# Sheet8.net
KiCad netlist of a schematic drawn in Altium Designer
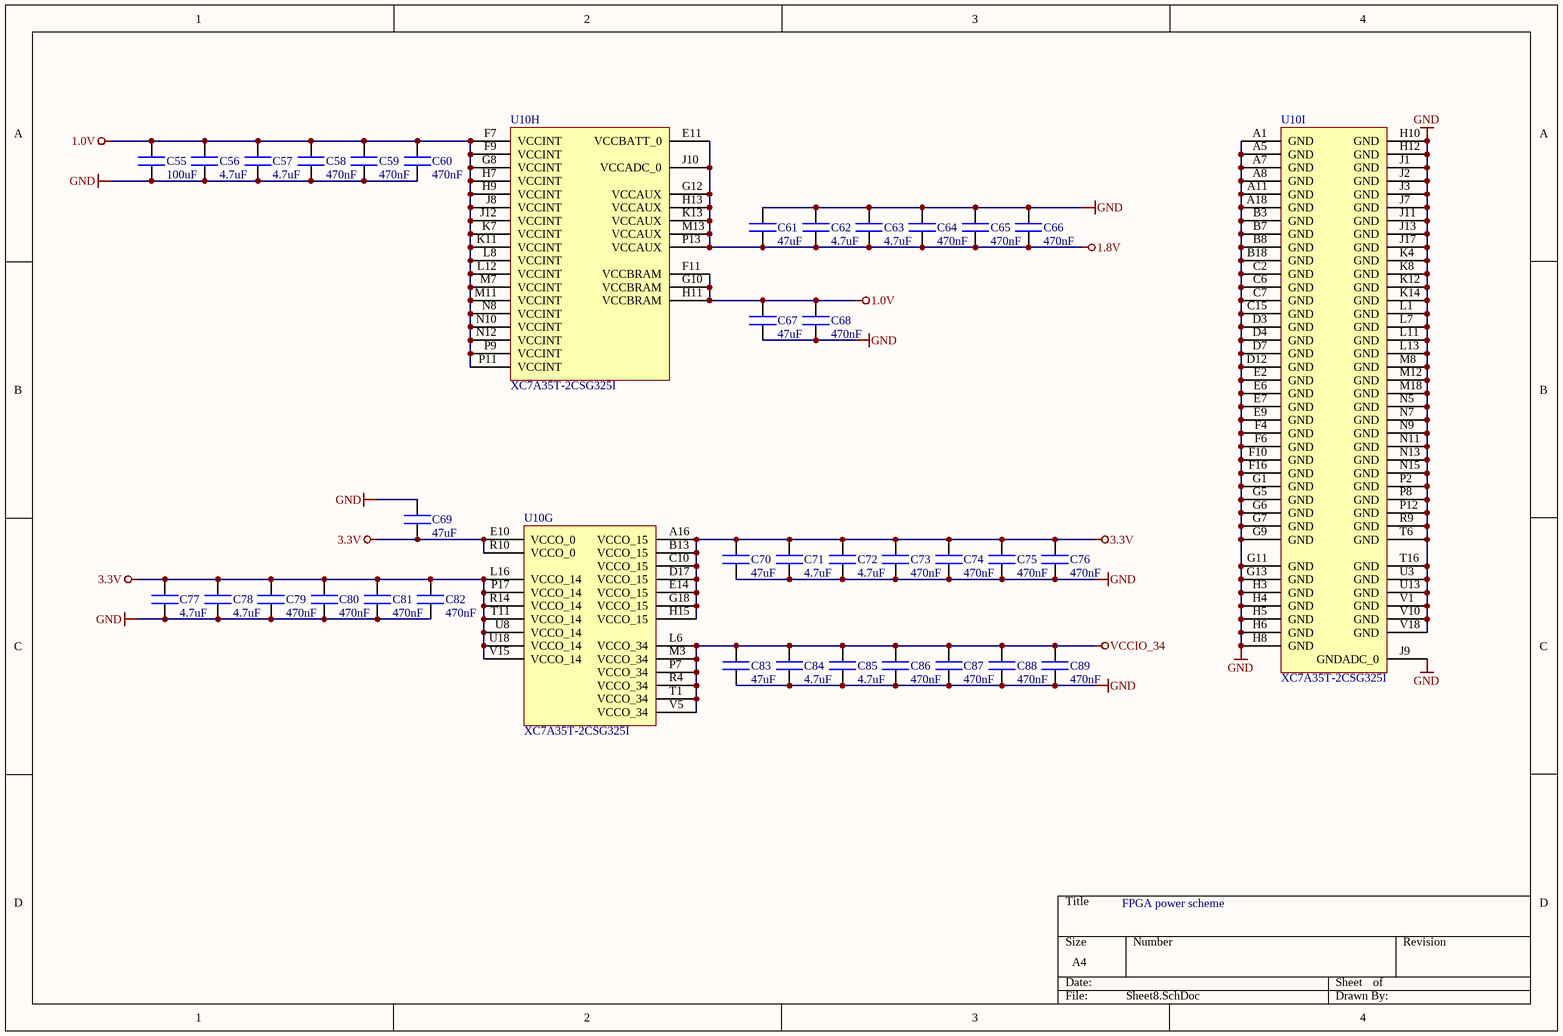
[diagram p0: Sheet8.SchDoc]

(export (version "E")
  (design (tool "Eeschema 10.0.6"))
  (components
    (comp (ref "C55")
      (value "100uF")
      (footprint "CAPC3216X16N")
      (description "Ceramic Chip Capacitor")
      (libsource (lib "Integrated_Library") (part "C1206"))
    )
    (comp (ref "C56")
      (value "4.7uF")
      (footprint "CAPC1005X05L")
      (description "Ceramic Chip Capacitor")
      (libsource (lib "Integrated_Library") (part "C0402"))
    )
    (comp (ref "C57")
      (value "4.7uF")
      (footprint "CAPC1005X05L")
      (description "Ceramic Chip Capacitor")
      (libsource (lib "Integrated_Library") (part "C0402"))
    )
    (comp (ref "C58")
      (value "470nF")
      (footprint "CAPC1005X05L")
      (description "Ceramic Chip Capacitor")
      (libsource (lib "Integrated_Library") (part "C0402"))
    )
    (comp (ref "C59")
      (value "470nF")
      (footprint "CAPC1005X05L")
      (description "Ceramic Chip Capacitor")
      (libsource (lib "Integrated_Library") (part "C0402"))
    )
    (comp (ref "C60")
      (value "470nF")
      (footprint "CAPC1005X05L")
      (description "Ceramic Chip Capacitor")
      (libsource (lib "Integrated_Library") (part "C0402"))
    )
    (comp (ref "C61")
      (value "47uF")
      (footprint "CAPC2012X12N")
      (description "Ceramic Chip Capacitor")
      (libsource (lib "Integrated_Library") (part "C0805"))
    )
    (comp (ref "C62")
      (value "4.7uF")
      (footprint "CAPC1005X05L")
      (description "Ceramic Chip Capacitor")
      (libsource (lib "Integrated_Library") (part "C0402"))
    )
    (comp (ref "C63")
      (value "4.7uF")
      (footprint "CAPC1005X05L")
      (description "Ceramic Chip Capacitor")
      (libsource (lib "Integrated_Library") (part "C0402"))
    )
    (comp (ref "C64")
      (value "470nF")
      (footprint "CAPC1005X05L")
      (description "Ceramic Chip Capacitor")
      (libsource (lib "Integrated_Library") (part "C0402"))
    )
    (comp (ref "C65")
      (value "470nF")
      (footprint "CAPC1005X05L")
      (description "Ceramic Chip Capacitor")
      (libsource (lib "Integrated_Library") (part "C0402"))
    )
    (comp (ref "C66")
      (value "470nF")
      (footprint "CAPC1005X05L")
      (description "Ceramic Chip Capacitor")
      (libsource (lib "Integrated_Library") (part "C0402"))
    )
    (comp (ref "C67")
      (value "47uF")
      (footprint "CAPC2012X12N")
      (description "Ceramic Chip Capacitor")
      (libsource (lib "Integrated_Library") (part "C0805"))
    )
    (comp (ref "C68")
      (value "470nF")
      (footprint "CAPC1005X05L")
      (description "Ceramic Chip Capacitor")
      (libsource (lib "Integrated_Library") (part "C0402"))
    )
    (comp (ref "C69")
      (value "47uF")
      (footprint "CAPC2012X12N")
      (description "Ceramic Chip Capacitor")
      (libsource (lib "Integrated_Library") (part "C0805"))
    )
    (comp (ref "C70")
      (value "47uF")
      (footprint "CAPC2012X12N")
      (description "Ceramic Chip Capacitor")
      (libsource (lib "Integrated_Library") (part "C0805"))
    )
    (comp (ref "C71")
      (value "4.7uF")
      (footprint "CAPC1005X05L")
      (description "Ceramic Chip Capacitor")
      (libsource (lib "Integrated_Library") (part "C0402"))
    )
    (comp (ref "C72")
      (value "4.7uF")
      (footprint "CAPC1005X05L")
      (description "Ceramic Chip Capacitor")
      (libsource (lib "Integrated_Library") (part "C0402"))
    )
    (comp (ref "C73")
      (value "470nF")
      (footprint "CAPC1005X05L")
      (description "Ceramic Chip Capacitor")
      (libsource (lib "Integrated_Library") (part "C0402"))
    )
    (comp (ref "C74")
      (value "470nF")
      (footprint "CAPC1005X05L")
      (description "Ceramic Chip Capacitor")
      (libsource (lib "Integrated_Library") (part "C0402"))
    )
    (comp (ref "C75")
      (value "470nF")
      (footprint "CAPC1005X05L")
      (description "Ceramic Chip Capacitor")
      (libsource (lib "Integrated_Library") (part "C0402"))
    )
    (comp (ref "C76")
      (value "470nF")
      (footprint "CAPC1005X05L")
      (description "Ceramic Chip Capacitor")
      (libsource (lib "Integrated_Library") (part "C0402"))
    )
    (comp (ref "C77")
      (value "4.7uF")
      (footprint "CAPC1005X05L")
      (description "Ceramic Chip Capacitor")
      (libsource (lib "Integrated_Library") (part "C0402"))
    )
    (comp (ref "C78")
      (value "4.7uF")
      (footprint "CAPC1005X05L")
      (description "Ceramic Chip Capacitor")
      (libsource (lib "Integrated_Library") (part "C0402"))
    )
    (comp (ref "C79")
      (value "470nF")
      (footprint "CAPC1005X05L")
      (description "Ceramic Chip Capacitor")
      (libsource (lib "Integrated_Library") (part "C0402"))
    )
    (comp (ref "C80")
      (value "470nF")
      (footprint "CAPC1005X05L")
      (description "Ceramic Chip Capacitor")
      (libsource (lib "Integrated_Library") (part "C0402"))
    )
    (comp (ref "C81")
      (value "470nF")
      (footprint "CAPC1005X05L")
      (description "Ceramic Chip Capacitor")
      (libsource (lib "Integrated_Library") (part "C0402"))
    )
    (comp (ref "C82")
      (value "470nF")
      (footprint "CAPC1005X05L")
      (description "Ceramic Chip Capacitor")
      (libsource (lib "Integrated_Library") (part "C0402"))
    )
    (comp (ref "C83")
      (value "47uF")
      (footprint "CAPC2012X12N")
      (description "Ceramic Chip Capacitor")
      (libsource (lib "Integrated_Library") (part "C0805"))
    )
    (comp (ref "C84")
      (value "4.7uF")
      (footprint "CAPC1005X05L")
      (description "Ceramic Chip Capacitor")
      (libsource (lib "Integrated_Library") (part "C0402"))
    )
    (comp (ref "C85")
      (value "4.7uF")
      (footprint "CAPC1005X05L")
      (description "Ceramic Chip Capacitor")
      (libsource (lib "Integrated_Library") (part "C0402"))
    )
    (comp (ref "C86")
      (value "470nF")
      (footprint "CAPC1005X05L")
      (description "Ceramic Chip Capacitor")
      (libsource (lib "Integrated_Library") (part "C0402"))
    )
    (comp (ref "C87")
      (value "470nF")
      (footprint "CAPC1005X05L")
      (description "Ceramic Chip Capacitor")
      (libsource (lib "Integrated_Library") (part "C0402"))
    )
    (comp (ref "C88")
      (value "470nF")
      (footprint "CAPC1005X05L")
      (description "Ceramic Chip Capacitor")
      (libsource (lib "Integrated_Library") (part "C0402"))
    )
    (comp (ref "C89")
      (value "470nF")
      (footprint "CAPC1005X05L")
      (description "Ceramic Chip Capacitor")
      (libsource (lib "Integrated_Library") (part "C0402"))
    )
    (comp (ref "U10")
      (value "XC7A35T-2CSG325I")
      (footprint "XC7A35T-2CSG325I")
      (description "Artix-7 FPGA, 150 User I/Os, 4 GTP, 324-Ball BGA, Speed Grade 2, Industrial Grade, Pb-Free")
      (fields (field (name "MANUFACTURER") "Xilinx"))
      (libsource (lib "Integrated_Library") (part "XC7A35T-2CSG325I"))
    )
  )
  (nets
    (net (code "1") (name "1.0V") (class "Default")
      (node (ref "C55") (pin "2") (pinfunction "2_2") (pintype "passive"))
      (node (ref "C56") (pin "2") (pinfunction "2_2") (pintype "passive"))
      (node (ref "C57") (pin "2") (pinfunction "2_2") (pintype "passive"))
      (node (ref "C58") (pin "2") (pinfunction "2_2") (pintype "passive"))
      (node (ref "C59") (pin "2") (pinfunction "2_2") (pintype "passive"))
      (node (ref "C60") (pin "2") (pinfunction "2_2") (pintype "passive"))
      (node (ref "C67") (pin "2") (pinfunction "2_2") (pintype "passive"))
      (node (ref "C68") (pin "1") (pinfunction "1_1") (pintype "passive"))
      (node (ref "U10") (pin "F11") (pinfunction "VCCBRAM_F11") (pintype "power_in"))
      (node (ref "U10") (pin "F7") (pinfunction "VCCINT_F7") (pintype "power_in"))
      (node (ref "U10") (pin "F9") (pinfunction "VCCINT_F9") (pintype "power_in"))
      (node (ref "U10") (pin "G10") (pinfunction "VCCBRAM_G10") (pintype "power_in"))
      (node (ref "U10") (pin "G8") (pinfunction "VCCINT_G8") (pintype "power_in"))
      (node (ref "U10") (pin "H11") (pinfunction "VCCBRAM_H11") (pintype "power_in"))
      (node (ref "U10") (pin "H7") (pinfunction "VCCINT_H7") (pintype "power_in"))
      (node (ref "U10") (pin "H9") (pinfunction "VCCINT_H9") (pintype "power_in"))
      (node (ref "U10") (pin "J12") (pinfunction "VCCINT_J12") (pintype "power_in"))
      (node (ref "U10") (pin "J8") (pinfunction "VCCINT_J8") (pintype "power_in"))
      (node (ref "U10") (pin "K11") (pinfunction "VCCINT_K11") (pintype "power_in"))
      (node (ref "U10") (pin "K7") (pinfunction "VCCINT_K7") (pintype "power_in"))
      (node (ref "U10") (pin "L12") (pinfunction "VCCINT_L12") (pintype "power_in"))
      (node (ref "U10") (pin "L8") (pinfunction "VCCINT_L8") (pintype "power_in"))
      (node (ref "U10") (pin "M11") (pinfunction "VCCINT_M11") (pintype "power_in"))
      (node (ref "U10") (pin "M7") (pinfunction "VCCINT_M7") (pintype "power_in"))
      (node (ref "U10") (pin "N10") (pinfunction "VCCINT_N10") (pintype "power_in"))
      (node (ref "U10") (pin "N12") (pinfunction "VCCINT_N12") (pintype "power_in"))
      (node (ref "U10") (pin "N8") (pinfunction "VCCINT_N8") (pintype "power_in"))
      (node (ref "U10") (pin "P11") (pinfunction "VCCINT_P11") (pintype "power_in"))
      (node (ref "U10") (pin "P9") (pinfunction "VCCINT_P9") (pintype "power_in"))
    )
    (net (code "2") (name "1.8V") (class "Default")
      (node (ref "C61") (pin "1") (pinfunction "1_1") (pintype "passive"))
      (node (ref "C62") (pin "1") (pinfunction "1_1") (pintype "passive"))
      (node (ref "C63") (pin "1") (pinfunction "1_1") (pintype "passive"))
      (node (ref "C64") (pin "1") (pinfunction "1_1") (pintype "passive"))
      (node (ref "C65") (pin "1") (pinfunction "1_1") (pintype "passive"))
      (node (ref "C66") (pin "1") (pinfunction "1_1") (pintype "passive"))
      (node (ref "U10") (pin "E11") (pinfunction "VCCBATT_0_E11") (pintype "power_in"))
      (node (ref "U10") (pin "G12") (pinfunction "VCCAUX_G12") (pintype "power_in"))
      (node (ref "U10") (pin "H13") (pinfunction "VCCAUX_H13") (pintype "power_in"))
      (node (ref "U10") (pin "J10") (pinfunction "VCCADC_0_J10") (pintype "power_in"))
      (node (ref "U10") (pin "K13") (pinfunction "VCCAUX_K13") (pintype "power_in"))
      (node (ref "U10") (pin "M13") (pinfunction "VCCAUX_M13") (pintype "power_in"))
      (node (ref "U10") (pin "P13") (pinfunction "VCCAUX_P13") (pintype "power_in"))
    )
    (net (code "3") (name "3.3V") (class "Default")
      (node (ref "C69") (pin "2") (pinfunction "2_2") (pintype "passive"))
      (node (ref "C70") (pin "2") (pinfunction "2_2") (pintype "passive"))
      (node (ref "C71") (pin "2") (pinfunction "2_2") (pintype "passive"))
      (node (ref "C72") (pin "2") (pinfunction "2_2") (pintype "passive"))
      (node (ref "C73") (pin "2") (pinfunction "2_2") (pintype "passive"))
      (node (ref "C74") (pin "2") (pinfunction "2_2") (pintype "passive"))
      (node (ref "C75") (pin "2") (pinfunction "2_2") (pintype "passive"))
      (node (ref "C76") (pin "2") (pinfunction "2_2") (pintype "passive"))
      (node (ref "C77") (pin "2") (pinfunction "2_2") (pintype "passive"))
      (node (ref "C78") (pin "2") (pinfunction "2_2") (pintype "passive"))
      (node (ref "C79") (pin "2") (pinfunction "2_2") (pintype "passive"))
      (node (ref "C80") (pin "2") (pinfunction "2_2") (pintype "passive"))
      (node (ref "C81") (pin "2") (pinfunction "2_2") (pintype "passive"))
      (node (ref "C82") (pin "2") (pinfunction "2_2") (pintype "passive"))
      (node (ref "U10") (pin "A16") (pinfunction "VCCO_15_A16") (pintype "power_in"))
      (node (ref "U10") (pin "B13") (pinfunction "VCCO_15_B13") (pintype "power_in"))
      (node (ref "U10") (pin "C10") (pinfunction "VCCO_15_C10") (pintype "power_in"))
      (node (ref "U10") (pin "D17") (pinfunction "VCCO_15_D17") (pintype "power_in"))
      (node (ref "U10") (pin "E10") (pinfunction "VCCO_0_E10") (pintype "power_in"))
      (node (ref "U10") (pin "E14") (pinfunction "VCCO_15_E14") (pintype "power_in"))
      (node (ref "U10") (pin "G18") (pinfunction "VCCO_15_G18") (pintype "power_in"))
      (node (ref "U10") (pin "H15") (pinfunction "VCCO_15_H15") (pintype "power_in"))
      (node (ref "U10") (pin "L16") (pinfunction "VCCO_14_L16") (pintype "power_in"))
      (node (ref "U10") (pin "P17") (pinfunction "VCCO_14_P17") (pintype "power_in"))
      (node (ref "U10") (pin "R10") (pinfunction "VCCO_0_R10") (pintype "power_in"))
      (node (ref "U10") (pin "R14") (pinfunction "VCCO_14_R14") (pintype "power_in"))
      (node (ref "U10") (pin "T11") (pinfunction "VCCO_14_T11") (pintype "power_in"))
      (node (ref "U10") (pin "U18") (pinfunction "VCCO_14_U18") (pintype "power_in"))
      (node (ref "U10") (pin "U8") (pinfunction "VCCO_14_U8") (pintype "power_in"))
      (node (ref "U10") (pin "V15") (pinfunction "VCCO_14_V15") (pintype "power_in"))
    )
    (net (code "4") (name "GND") (class "Default")
      (node (ref "C55") (pin "1") (pinfunction "1_1") (pintype "passive"))
      (node (ref "C56") (pin "1") (pinfunction "1_1") (pintype "passive"))
      (node (ref "C57") (pin "1") (pinfunction "1_1") (pintype "passive"))
      (node (ref "C58") (pin "1") (pinfunction "1_1") (pintype "passive"))
      (node (ref "C59") (pin "1") (pinfunction "1_1") (pintype "passive"))
      (node (ref "C60") (pin "1") (pinfunction "1_1") (pintype "passive"))
      (node (ref "C61") (pin "2") (pinfunction "2_2") (pintype "passive"))
      (node (ref "C62") (pin "2") (pinfunction "2_2") (pintype "passive"))
      (node (ref "C63") (pin "2") (pinfunction "2_2") (pintype "passive"))
      (node (ref "C64") (pin "2") (pinfunction "2_2") (pintype "passive"))
      (node (ref "C65") (pin "2") (pinfunction "2_2") (pintype "passive"))
      (node (ref "C66") (pin "2") (pinfunction "2_2") (pintype "passive"))
      (node (ref "C67") (pin "1") (pinfunction "1_1") (pintype "passive"))
      (node (ref "C68") (pin "2") (pinfunction "2_2") (pintype "passive"))
      (node (ref "C69") (pin "1") (pinfunction "1_1") (pintype "passive"))
      (node (ref "C70") (pin "1") (pinfunction "1_1") (pintype "passive"))
      (node (ref "C71") (pin "1") (pinfunction "1_1") (pintype "passive"))
      (node (ref "C72") (pin "1") (pinfunction "1_1") (pintype "passive"))
      (node (ref "C73") (pin "1") (pinfunction "1_1") (pintype "passive"))
      (node (ref "C74") (pin "1") (pinfunction "1_1") (pintype "passive"))
      (node (ref "C75") (pin "1") (pinfunction "1_1") (pintype "passive"))
      (node (ref "C76") (pin "1") (pinfunction "1_1") (pintype "passive"))
      (node (ref "C77") (pin "1") (pinfunction "1_1") (pintype "passive"))
      (node (ref "C78") (pin "1") (pinfunction "1_1") (pintype "passive"))
      (node (ref "C79") (pin "1") (pinfunction "1_1") (pintype "passive"))
      (node (ref "C80") (pin "1") (pinfunction "1_1") (pintype "passive"))
      (node (ref "C81") (pin "1") (pinfunction "1_1") (pintype "passive"))
      (node (ref "C82") (pin "1") (pinfunction "1_1") (pintype "passive"))
      (node (ref "C83") (pin "1") (pinfunction "1_1") (pintype "passive"))
      (node (ref "C84") (pin "1") (pinfunction "1_1") (pintype "passive"))
      (node (ref "C85") (pin "1") (pinfunction "1_1") (pintype "passive"))
      (node (ref "C86") (pin "1") (pinfunction "1_1") (pintype "passive"))
      (node (ref "C87") (pin "1") (pinfunction "1_1") (pintype "passive"))
      (node (ref "C88") (pin "1") (pinfunction "1_1") (pintype "passive"))
      (node (ref "C89") (pin "1") (pinfunction "1_1") (pintype "passive"))
      (node (ref "U10") (pin "A1") (pinfunction "GND_A1") (pintype "power_in"))
      (node (ref "U10") (pin "A11") (pinfunction "GND_A11") (pintype "power_in"))
      (node (ref "U10") (pin "A18") (pinfunction "GND_A18") (pintype "power_in"))
      (node (ref "U10") (pin "A5") (pinfunction "GND_A5") (pintype "power_in"))
      (node (ref "U10") (pin "A7") (pinfunction "GND_A7") (pintype "power_in"))
      (node (ref "U10") (pin "A8") (pinfunction "GND_A8") (pintype "power_in"))
      (node (ref "U10") (pin "B18") (pinfunction "GND_B18") (pintype "power_in"))
      (node (ref "U10") (pin "B3") (pinfunction "GND_B3") (pintype "power_in"))
      (node (ref "U10") (pin "B7") (pinfunction "GND_B7") (pintype "power_in"))
      (node (ref "U10") (pin "B8") (pinfunction "GND_B8") (pintype "power_in"))
      (node (ref "U10") (pin "C15") (pinfunction "GND_C15") (pintype "power_in"))
      (node (ref "U10") (pin "C2") (pinfunction "GND_C2") (pintype "power_in"))
      (node (ref "U10") (pin "C6") (pinfunction "GND_C6") (pintype "power_in"))
      (node (ref "U10") (pin "C7") (pinfunction "GND_C7") (pintype "power_in"))
      (node (ref "U10") (pin "D12") (pinfunction "GND_D12") (pintype "power_in"))
      (node (ref "U10") (pin "D3") (pinfunction "GND_D3") (pintype "power_in"))
      (node (ref "U10") (pin "D4") (pinfunction "GND_D4") (pintype "power_in"))
      (node (ref "U10") (pin "D7") (pinfunction "GND_D7") (pintype "power_in"))
      (node (ref "U10") (pin "E2") (pinfunction "GND_E2") (pintype "power_in"))
      (node (ref "U10") (pin "E6") (pinfunction "GND_E6") (pintype "power_in"))
      (node (ref "U10") (pin "E7") (pinfunction "GND_E7") (pintype "power_in"))
      (node (ref "U10") (pin "E9") (pinfunction "GND_E9") (pintype "power_in"))
      (node (ref "U10") (pin "F10") (pinfunction "GND_F10") (pintype "power_in"))
      (node (ref "U10") (pin "F16") (pinfunction "GND_F16") (pintype "power_in"))
      (node (ref "U10") (pin "F4") (pinfunction "GND_F4") (pintype "power_in"))
      (node (ref "U10") (pin "F6") (pinfunction "GND_F6") (pintype "power_in"))
      (node (ref "U10") (pin "G1") (pinfunction "GND_G1") (pintype "power_in"))
      (node (ref "U10") (pin "G11") (pinfunction "GND_G11") (pintype "power_in"))
      (node (ref "U10") (pin "G13") (pinfunction "GND_G13") (pintype "power_in"))
      (node (ref "U10") (pin "G5") (pinfunction "GND_G5") (pintype "power_in"))
      (node (ref "U10") (pin "G6") (pinfunction "GND_G6") (pintype "power_in"))
      (node (ref "U10") (pin "G7") (pinfunction "GND_G7") (pintype "power_in"))
      (node (ref "U10") (pin "G9") (pinfunction "GND_G9") (pintype "power_in"))
      (node (ref "U10") (pin "H10") (pinfunction "GND_H10") (pintype "power_in"))
      (node (ref "U10") (pin "H12") (pinfunction "GND_H12") (pintype "power_in"))
      (node (ref "U10") (pin "H3") (pinfunction "GND_H3") (pintype "power_in"))
      (node (ref "U10") (pin "H4") (pinfunction "GND_H4") (pintype "power_in"))
      (node (ref "U10") (pin "H5") (pinfunction "GND_H5") (pintype "power_in"))
      (node (ref "U10") (pin "H6") (pinfunction "GND_H6") (pintype "power_in"))
      (node (ref "U10") (pin "H8") (pinfunction "GND_H8") (pintype "power_in"))
      (node (ref "U10") (pin "J1") (pinfunction "GND_J1") (pintype "power_in"))
      (node (ref "U10") (pin "J11") (pinfunction "GND_J11") (pintype "power_in"))
      (node (ref "U10") (pin "J13") (pinfunction "GND_J13") (pintype "power_in"))
      (node (ref "U10") (pin "J17") (pinfunction "GND_J17") (pintype "power_in"))
      (node (ref "U10") (pin "J2") (pinfunction "GND_J2") (pintype "power_in"))
      (node (ref "U10") (pin "J3") (pinfunction "GND_J3") (pintype "power_in"))
      (node (ref "U10") (pin "J7") (pinfunction "GND_J7") (pintype "power_in"))
      (node (ref "U10") (pin "J9") (pinfunction "GNDADC_0_J9") (pintype "power_in"))
      (node (ref "U10") (pin "K12") (pinfunction "GND_K12") (pintype "power_in"))
      (node (ref "U10") (pin "K14") (pinfunction "GND_K14") (pintype "power_in"))
      (node (ref "U10") (pin "K4") (pinfunction "GND_K4") (pintype "power_in"))
      (node (ref "U10") (pin "K8") (pinfunction "GND_K8") (pintype "power_in"))
      (node (ref "U10") (pin "L1") (pinfunction "GND_L1") (pintype "power_in"))
      (node (ref "U10") (pin "L11") (pinfunction "GND_L11") (pintype "power_in"))
      (node (ref "U10") (pin "L13") (pinfunction "GND_L13") (pintype "power_in"))
      (node (ref "U10") (pin "L7") (pinfunction "GND_L7") (pintype "power_in"))
      (node (ref "U10") (pin "M12") (pinfunction "GND_M12") (pintype "power_in"))
      (node (ref "U10") (pin "M18") (pinfunction "GND_M18") (pintype "power_in"))
      (node (ref "U10") (pin "M8") (pinfunction "GND_M8") (pintype "power_in"))
      (node (ref "U10") (pin "N11") (pinfunction "GND_N11") (pintype "power_in"))
      (node (ref "U10") (pin "N13") (pinfunction "GND_N13") (pintype "power_in"))
      (node (ref "U10") (pin "N15") (pinfunction "GND_N15") (pintype "power_in"))
      (node (ref "U10") (pin "N5") (pinfunction "GND_N5") (pintype "power_in"))
      (node (ref "U10") (pin "N7") (pinfunction "GND_N7") (pintype "power_in"))
      (node (ref "U10") (pin "N9") (pinfunction "GND_N9") (pintype "power_in"))
      (node (ref "U10") (pin "P12") (pinfunction "GND_P12") (pintype "power_in"))
      (node (ref "U10") (pin "P2") (pinfunction "GND_P2") (pintype "power_in"))
      (node (ref "U10") (pin "P8") (pinfunction "GND_P8") (pintype "power_in"))
      (node (ref "U10") (pin "R9") (pinfunction "GND_R9") (pintype "power_in"))
      (node (ref "U10") (pin "T16") (pinfunction "GND_T16") (pintype "power_in"))
      (node (ref "U10") (pin "T6") (pinfunction "GND_T6") (pintype "power_in"))
      (node (ref "U10") (pin "U13") (pinfunction "GND_U13") (pintype "power_in"))
      (node (ref "U10") (pin "U3") (pinfunction "GND_U3") (pintype "power_in"))
      (node (ref "U10") (pin "V1") (pinfunction "GND_V1") (pintype "power_in"))
      (node (ref "U10") (pin "V10") (pinfunction "GND_V10") (pintype "power_in"))
      (node (ref "U10") (pin "V18") (pinfunction "GND_V18") (pintype "power_in"))
    )
    (net (code "5") (name "VCCIO_34") (class "Default")
      (node (ref "C83") (pin "2") (pinfunction "2_2") (pintype "passive"))
      (node (ref "C84") (pin "2") (pinfunction "2_2") (pintype "passive"))
      (node (ref "C85") (pin "2") (pinfunction "2_2") (pintype "passive"))
      (node (ref "C86") (pin "2") (pinfunction "2_2") (pintype "passive"))
      (node (ref "C87") (pin "2") (pinfunction "2_2") (pintype "passive"))
      (node (ref "C88") (pin "2") (pinfunction "2_2") (pintype "passive"))
      (node (ref "C89") (pin "2") (pinfunction "2_2") (pintype "passive"))
      (node (ref "U10") (pin "L6") (pinfunction "VCCO_34_L6") (pintype "power_in"))
      (node (ref "U10") (pin "M3") (pinfunction "VCCO_34_M3") (pintype "power_in"))
      (node (ref "U10") (pin "P7") (pinfunction "VCCO_34_P7") (pintype "power_in"))
      (node (ref "U10") (pin "R4") (pinfunction "VCCO_34_R4") (pintype "power_in"))
      (node (ref "U10") (pin "T1") (pinfunction "VCCO_34_T1") (pintype "power_in"))
      (node (ref "U10") (pin "V5") (pinfunction "VCCO_34_V5") (pintype "power_in"))
    )
  )
)
